# SCH_Altimeter1_2026-02-15.net
KiCad netlist of a schematic drawn in EasyEDA
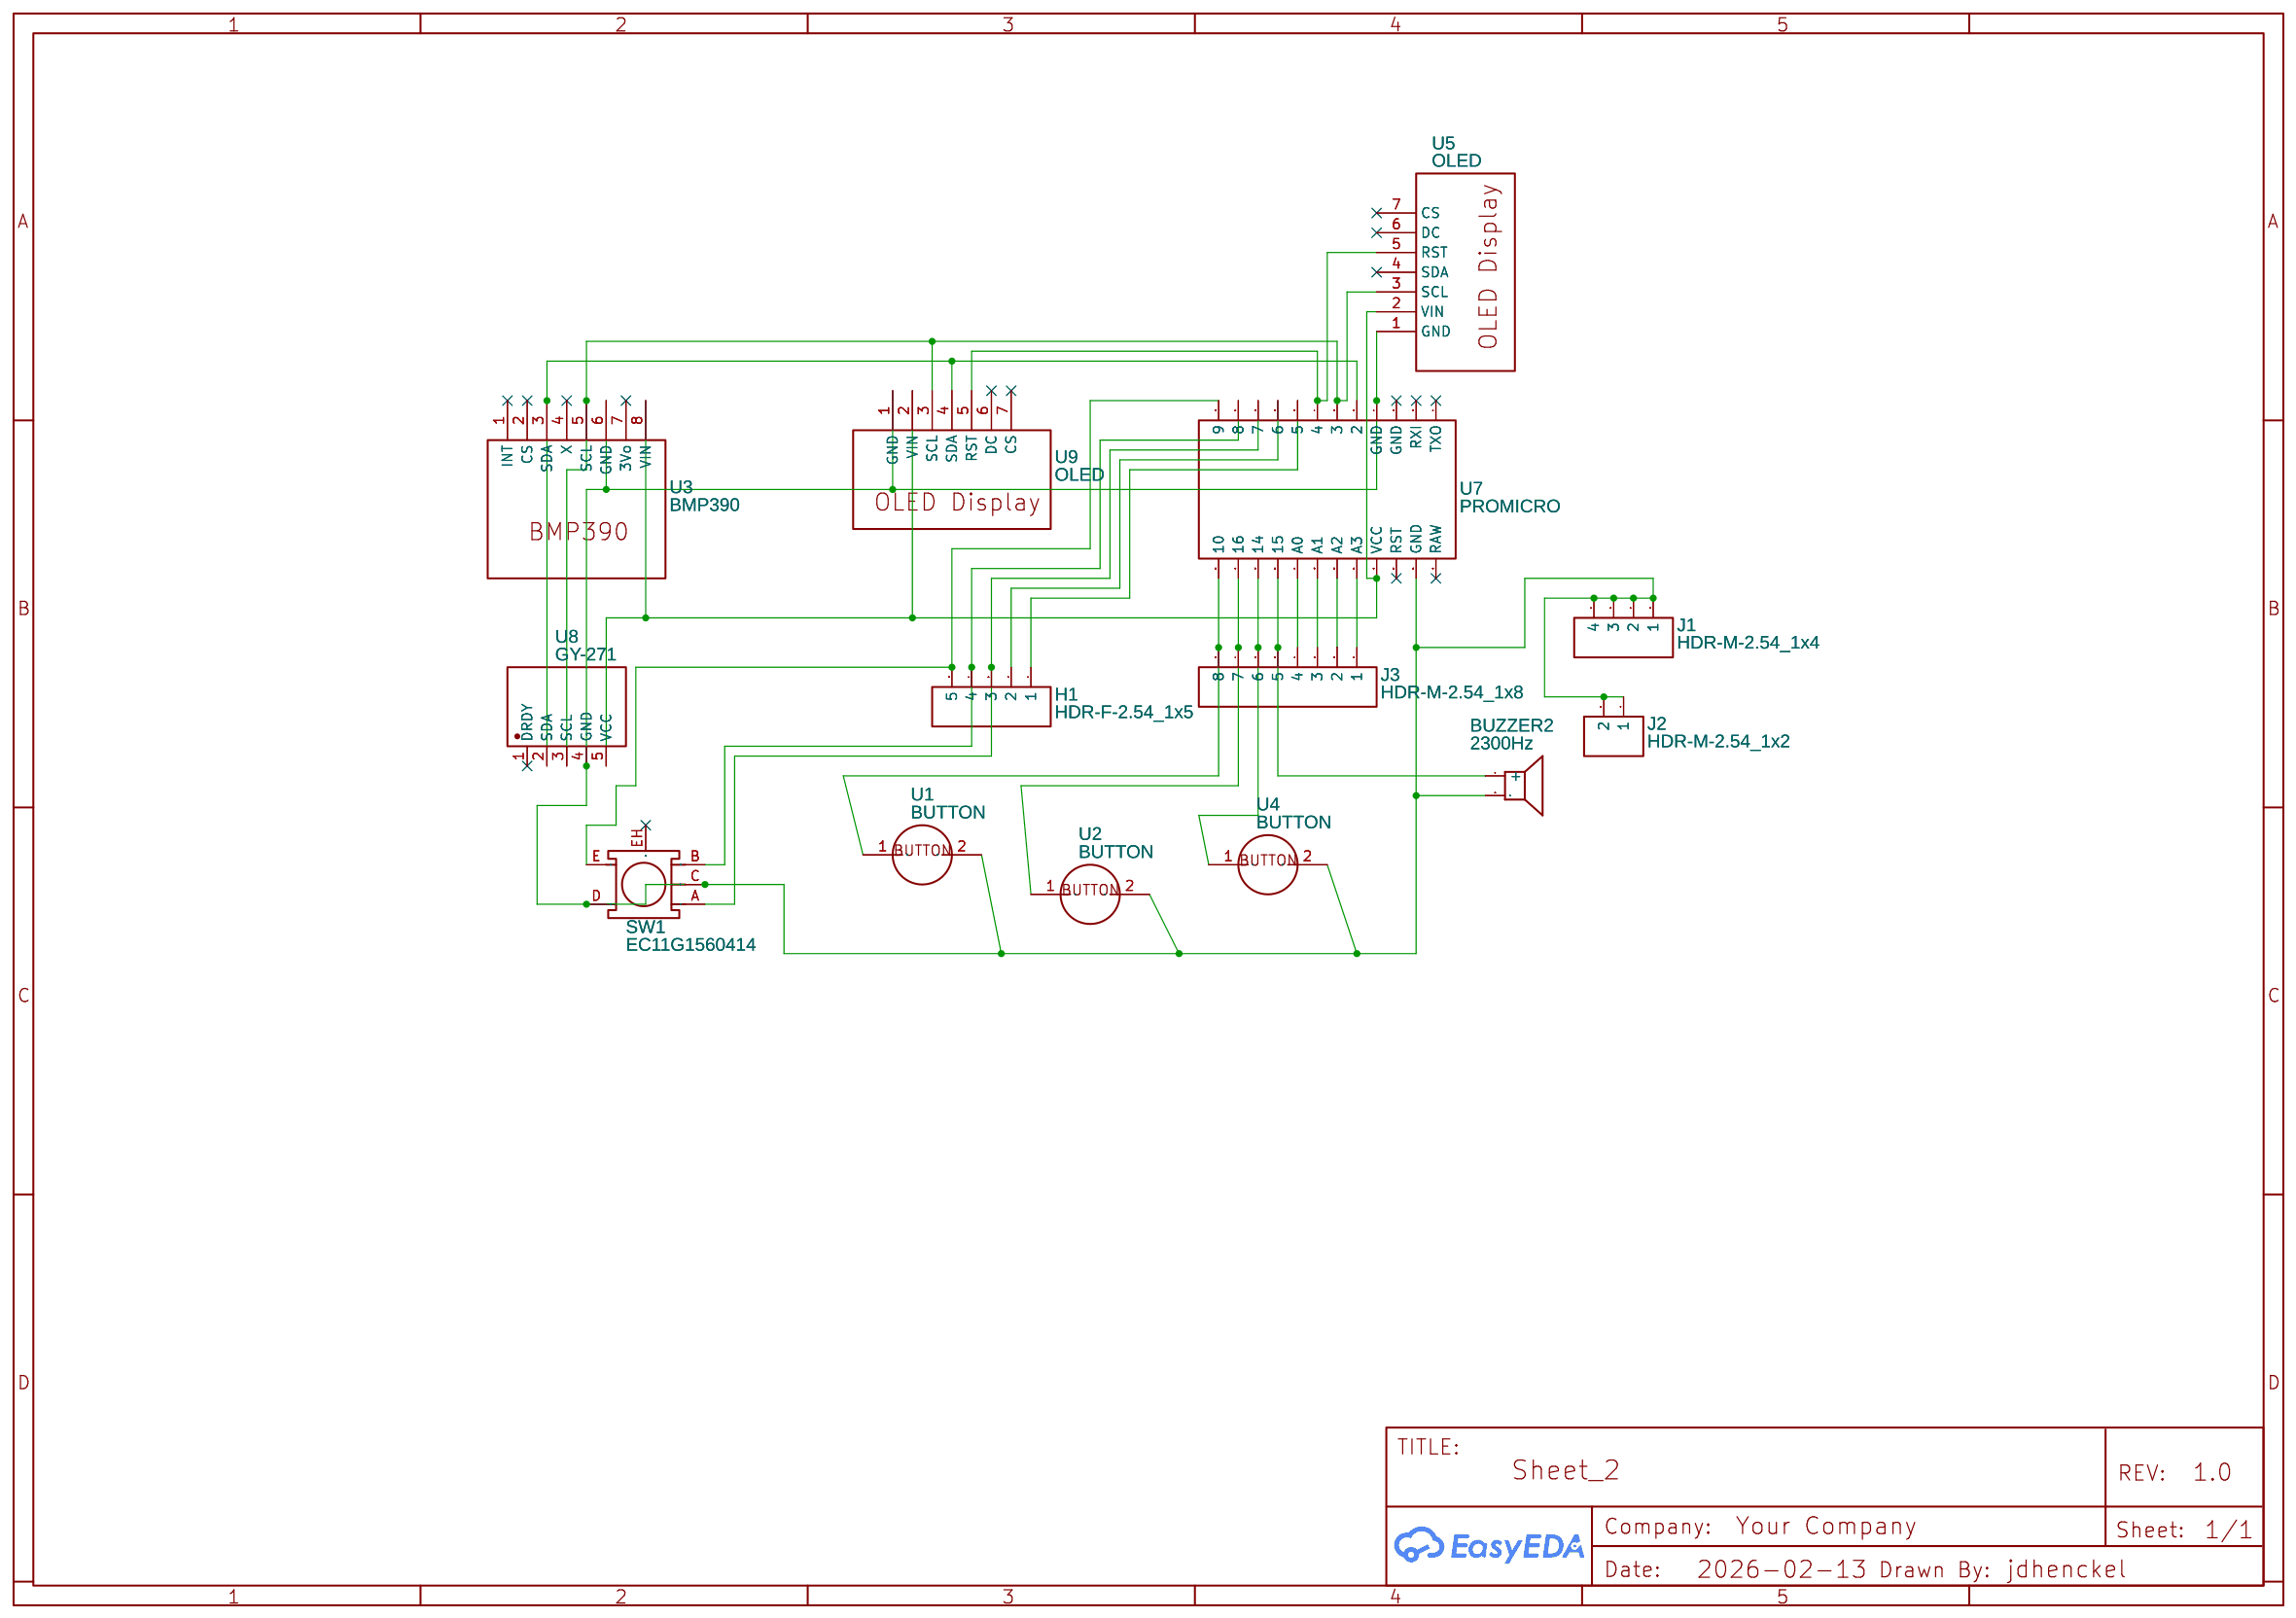
[diagram p0: schematic sheet]

(export (version "E")
  (design (tool "Eeschema 10.0.6"))
  (components
    (comp (ref "BUZZER2")
      (value "2300Hz")
      (fields (field (name "Manufacturer Part") "TMB12A03") (field (name "Manufacturer") "华能"))
      (libsource (lib "") (part "TMB12A03"))
    )
    (comp (ref "H1") (value "HDR-F-2.54_1x5") (libsource (lib "") (part "HDR-F-2.54_1x5")))
    (comp (ref "J1") (value "HDR-M-2.54_1x4") (libsource (lib "") (part "HDR-M-2.54_1x4")))
    (comp (ref "J2") (value "HDR-M-2.54_1x2") (libsource (lib "") (part "HDR-M-2.54_1x2")))
    (comp (ref "J3") (value "HDR-M-2.54_1x8") (libsource (lib "") (part "HDR-M-2.54_1x8")))
    (comp (ref "SW1")
      (value "EC11G1560414")
      (fields (field (name "Manufacturer") "ALPSALPINE(阿尔卑斯阿尔派)"))
      (libsource (lib "") (part "EC11G1560414"))
    )
    (comp (ref "U1") (value "BUTTON") (libsource (lib "") (part "BUTTON")))
    (comp (ref "U2") (value "BUTTON") (libsource (lib "") (part "BUTTON")))
    (comp (ref "U3") (value "BMP390") (libsource (lib "") (part "BMP390")))
    (comp (ref "U4") (value "BUTTON") (libsource (lib "") (part "BUTTON")))
    (comp (ref "U5") (value "OLED") (libsource (lib "") (part "OLED")))
    (comp (ref "U7") (value "PROMICRO") (libsource (lib "") (part "PROMICRO")))
    (comp (ref "U8") (value "GY-271") (libsource (lib "") (part "GY-271")))
    (comp (ref "U9") (value "OLED") (libsource (lib "") (part "OLED_1")))
  )
  (nets
    (net (code "1") (name "Net-(BUZZER2-+)") (class "Default")
      (node (ref "BUZZER2") (pin "1") (pinfunction "+_1") (pintype "unspecified"))
      (node (ref "J3") (pin "5") (pinfunction "5_5") (pintype "unspecified"))
      (node (ref "U7") (pin "16") (pinfunction "15_16") (pintype "unspecified"))
    )
    (net (code "2") (name "Net-(U3-GND)") (class "Default")
      (node (ref "BUZZER2") (pin "2") (pinfunction "2_2") (pintype "unspecified"))
      (node (ref "J1") (pin "1") (pinfunction "1_1") (pintype "unspecified"))
      (node (ref "J1") (pin "2") (pinfunction "2_2") (pintype "unspecified"))
      (node (ref "J1") (pin "3") (pinfunction "3_3") (pintype "unspecified"))
      (node (ref "J1") (pin "4") (pinfunction "4_4") (pintype "unspecified"))
      (node (ref "J2") (pin "1") (pinfunction "1_1") (pintype "unspecified"))
      (node (ref "J2") (pin "2") (pinfunction "2_2") (pintype "unspecified"))
      (node (ref "SW1") (pin "C") (pinfunction "C_C") (pintype "unspecified"))
      (node (ref "SW1") (pin "D") (pinfunction "D_D") (pintype "unspecified"))
      (node (ref "U1") (pin "2") (pinfunction "2_2") (pintype "unspecified"))
      (node (ref "U2") (pin "2") (pinfunction "2_2") (pintype "unspecified"))
      (node (ref "U3") (pin "6") (pinfunction "GND_6") (pintype "unspecified"))
      (node (ref "U4") (pin "2") (pinfunction "2_2") (pintype "unspecified"))
      (node (ref "U5") (pin "1") (pinfunction "GND_1") (pintype "unspecified"))
      (node (ref "U7") (pin "23") (pinfunction "GND_23") (pintype "unspecified"))
      (node (ref "U7") (pin "4") (pinfunction "GND_4") (pintype "unspecified"))
      (node (ref "U8") (pin "4") (pinfunction "GND_4") (pintype "unspecified"))
      (node (ref "U9") (pin "1") (pinfunction "GND_1") (pintype "unspecified"))
    )
    (net (code "3") (name "Net-(U3-SCL)") (class "Default")
      (node (ref "U3") (pin "5") (pinfunction "SCL_5") (pintype "unspecified"))
      (node (ref "U5") (pin "3") (pinfunction "SCL_3") (pintype "unspecified"))
      (node (ref "U7") (pin "6") (pinfunction "3_6") (pintype "unspecified"))
      (node (ref "U8") (pin "3") (pinfunction "SCL_3") (pintype "unspecified"))
      (node (ref "U9") (pin "3") (pinfunction "SCL_3") (pintype "unspecified"))
    )
    (net (code "4") (name "Net-(U3-SDA)") (class "Default")
      (node (ref "U3") (pin "3") (pinfunction "SDA_3") (pintype "unspecified"))
      (node (ref "U7") (pin "5") (pinfunction "2_5") (pintype "unspecified"))
      (node (ref "U8") (pin "2") (pinfunction "SDA_2") (pintype "unspecified"))
      (node (ref "U9") (pin "4") (pinfunction "SDA_4") (pintype "unspecified"))
    )
    (net (code "5") (name "Net-(U3-VIN)") (class "Default")
      (node (ref "U3") (pin "8") (pinfunction "VIN_8") (pintype "unspecified"))
      (node (ref "U5") (pin "2") (pinfunction "VIN_2") (pintype "unspecified"))
      (node (ref "U7") (pin "21") (pinfunction "VCC_21") (pintype "unspecified"))
      (node (ref "U8") (pin "5") (pinfunction "VCC_5") (pintype "unspecified"))
      (node (ref "U9") (pin "2") (pinfunction "VIN_2") (pintype "unspecified"))
    )
    (net (code "6") (name "Net-(U5-RST)") (class "Default")
      (node (ref "U5") (pin "5") (pinfunction "RST_5") (pintype "unspecified"))
      (node (ref "U7") (pin "7") (pinfunction "4_7") (pintype "unspecified"))
      (node (ref "U9") (pin "5") (pinfunction "RST_5") (pintype "unspecified"))
    )
    (net (code "7") (name "Net-(U7-5)") (class "Default")
      (node (ref "H1") (pin "1") (pinfunction "1_1") (pintype "unspecified"))
      (node (ref "U7") (pin "8") (pinfunction "5_8") (pintype "unspecified"))
    )
    (net (code "8") (name "Net-(U7-6)") (class "Default")
      (node (ref "H1") (pin "2") (pinfunction "2_2") (pintype "unspecified"))
      (node (ref "U7") (pin "9") (pinfunction "6_9") (pintype "unspecified"))
    )
    (net (code "9") (name "Net-(U7-7)") (class "Default")
      (node (ref "H1") (pin "3") (pinfunction "3_3") (pintype "unspecified"))
      (node (ref "SW1") (pin "A") (pinfunction "A_A") (pintype "unspecified"))
      (node (ref "U7") (pin "10") (pinfunction "7_10") (pintype "unspecified"))
    )
    (net (code "10") (name "Net-(U7-8)") (class "Default")
      (node (ref "H1") (pin "4") (pinfunction "4_4") (pintype "unspecified"))
      (node (ref "SW1") (pin "B") (pinfunction "B_B") (pintype "unspecified"))
      (node (ref "U7") (pin "11") (pinfunction "8_11") (pintype "unspecified"))
    )
    (net (code "11") (name "Net-(U7-9)") (class "Default")
      (node (ref "H1") (pin "5") (pinfunction "5_5") (pintype "unspecified"))
      (node (ref "SW1") (pin "E") (pinfunction "E_E") (pintype "unspecified"))
      (node (ref "U7") (pin "12") (pinfunction "9_12") (pintype "unspecified"))
    )
    (net (code "12") (name "Net-(U7-10)") (class "Default")
      (node (ref "J3") (pin "8") (pinfunction "8_8") (pintype "unspecified"))
      (node (ref "U1") (pin "1") (pinfunction "1_1") (pintype "unspecified"))
      (node (ref "U7") (pin "13") (pinfunction "10_13") (pintype "unspecified"))
    )
    (net (code "13") (name "Net-(U7-14)") (class "Default")
      (node (ref "J3") (pin "6") (pinfunction "6_6") (pintype "unspecified"))
      (node (ref "U4") (pin "1") (pinfunction "1_1") (pintype "unspecified"))
      (node (ref "U7") (pin "15") (pinfunction "14_15") (pintype "unspecified"))
    )
    (net (code "14") (name "Net-(U7-16)") (class "Default")
      (node (ref "J3") (pin "7") (pinfunction "7_7") (pintype "unspecified"))
      (node (ref "U2") (pin "1") (pinfunction "1_1") (pintype "unspecified"))
      (node (ref "U7") (pin "14") (pinfunction "16_14") (pintype "unspecified"))
    )
    (net (code "15") (name "Net-(U7-A0)") (class "Default")
      (node (ref "J3") (pin "4") (pinfunction "4_4") (pintype "unspecified"))
      (node (ref "U7") (pin "17") (pinfunction "A0_17") (pintype "unspecified"))
    )
    (net (code "16") (name "Net-(U7-A1)") (class "Default")
      (node (ref "J3") (pin "3") (pinfunction "3_3") (pintype "unspecified"))
      (node (ref "U7") (pin "18") (pinfunction "A1_18") (pintype "unspecified"))
    )
    (net (code "17") (name "Net-(U7-A2)") (class "Default")
      (node (ref "J3") (pin "2") (pinfunction "2_2") (pintype "unspecified"))
      (node (ref "U7") (pin "19") (pinfunction "A2_19") (pintype "unspecified"))
    )
    (net (code "18") (name "Net-(U7-A3)") (class "Default")
      (node (ref "J3") (pin "1") (pinfunction "1_1") (pintype "unspecified"))
      (node (ref "U7") (pin "20") (pinfunction "A3_20") (pintype "unspecified"))
    )
    (net (code "19") (name "unconnected-(SW1-PadEH)") (class "Default")
      (node (ref "SW1") (pin "EH") (pinfunction "EH_EH") (pintype "unspecified+no_connect"))
    )
    (net (code "20") (name "unconnected-(U3-3Vo-Pad7)") (class "Default")
      (node (ref "U3") (pin "7") (pinfunction "3Vo_7") (pintype "unspecified+no_connect"))
    )
    (net (code "21") (name "unconnected-(U3-CS-Pad2)") (class "Default")
      (node (ref "U3") (pin "2") (pinfunction "CS_2") (pintype "unspecified+no_connect"))
    )
    (net (code "22") (name "unconnected-(U3-INT-Pad1)") (class "Default")
      (node (ref "U3") (pin "1") (pinfunction "INT_1") (pintype "unspecified+no_connect"))
    )
    (net (code "23") (name "unconnected-(U3-X-Pad4)") (class "Default")
      (node (ref "U3") (pin "4") (pinfunction "X_4") (pintype "unspecified+no_connect"))
    )
    (net (code "24") (name "unconnected-(U5-CS-Pad7)") (class "Default")
      (node (ref "U5") (pin "7") (pinfunction "CS_7") (pintype "unspecified+no_connect"))
    )
    (net (code "25") (name "unconnected-(U5-DC-Pad6)") (class "Default")
      (node (ref "U5") (pin "6") (pinfunction "DC_6") (pintype "unspecified+no_connect"))
    )
    (net (code "26") (name "unconnected-(U5-SDA-Pad4)") (class "Default")
      (node (ref "U5") (pin "4") (pinfunction "SDA_4") (pintype "unspecified+no_connect"))
    )
    (net (code "27") (name "unconnected-(U7-GND-Pad3)") (class "Default")
      (node (ref "U7") (pin "3") (pinfunction "GND_3") (pintype "unspecified+no_connect"))
    )
    (net (code "28") (name "unconnected-(U7-RAW-Pad24)") (class "Default")
      (node (ref "U7") (pin "24") (pinfunction "RAW_24") (pintype "unspecified+no_connect"))
    )
    (net (code "29") (name "unconnected-(U7-RST-Pad22)") (class "Default")
      (node (ref "U7") (pin "22") (pinfunction "RST_22") (pintype "unspecified+no_connect"))
    )
    (net (code "30") (name "unconnected-(U7-RXI-Pad2)") (class "Default")
      (node (ref "U7") (pin "2") (pinfunction "RXI_2") (pintype "unspecified+no_connect"))
    )
    (net (code "31") (name "unconnected-(U7-TXO-Pad1)") (class "Default")
      (node (ref "U7") (pin "1") (pinfunction "TXO_1") (pintype "unspecified+no_connect"))
    )
    (net (code "32") (name "unconnected-(U8-DRDY-Pad1)") (class "Default")
      (node (ref "U8") (pin "1") (pinfunction "DRDY_1") (pintype "unspecified+no_connect"))
    )
    (net (code "33") (name "unconnected-(U9-CS-Pad7)") (class "Default")
      (node (ref "U9") (pin "7") (pinfunction "CS_7") (pintype "unspecified+no_connect"))
    )
    (net (code "34") (name "unconnected-(U9-DC-Pad6)") (class "Default")
      (node (ref "U9") (pin "6") (pinfunction "DC_6") (pintype "unspecified+no_connect"))
    )
  )
)
